# Buck.net
KiCad netlist of a schematic drawn in EAGLE
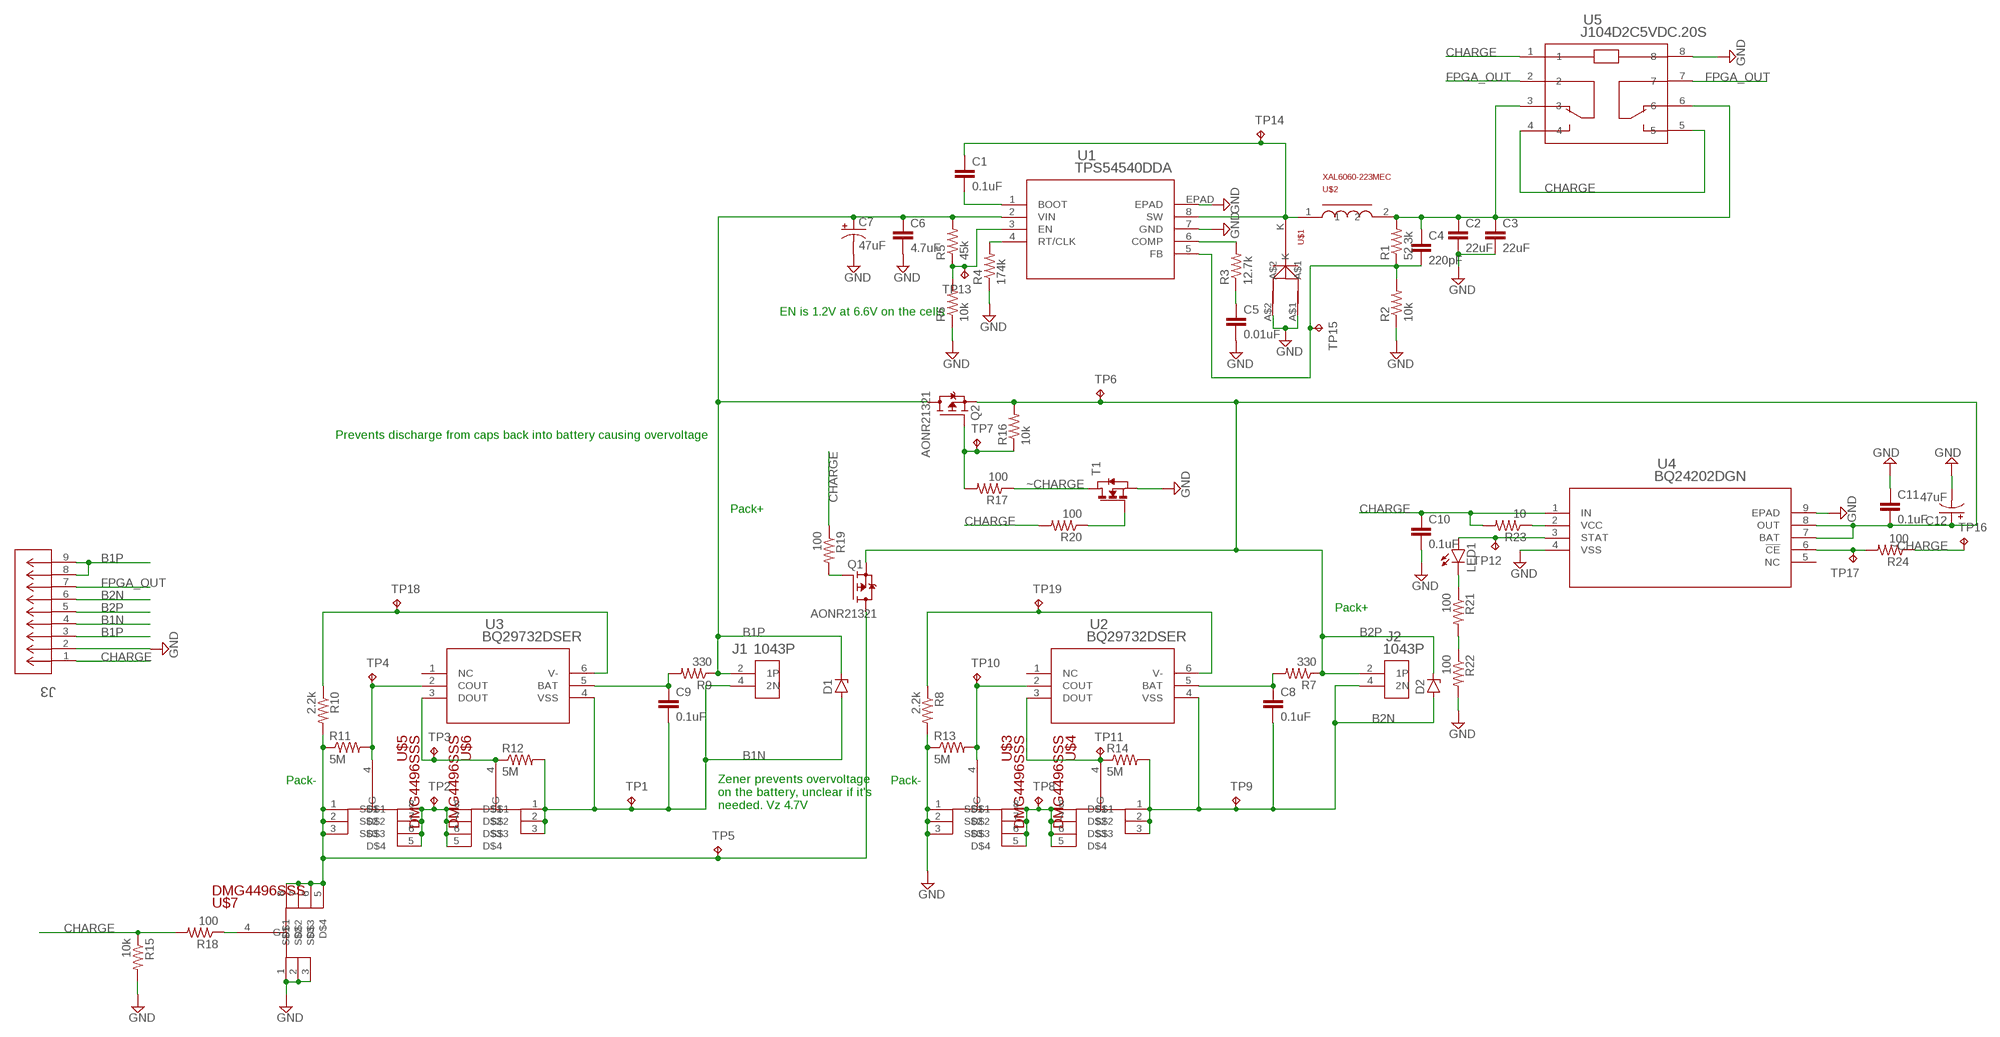
[diagram p0: schematic, sheet 1]

(export (version "E")
  (design (tool "Eeschema 10.0.6"))
  (components
    (comp (ref "C1")
      (value "0.1uF")
      (footprint "eagle-import:C0603")
      (libsource (lib "eagle-import") (part "C-EUC0603"))
    )
    (comp (ref "C2")
      (value "22uF")
      (footprint "eagle-import:C0603")
      (libsource (lib "eagle-import") (part "C-EUC0603"))
    )
    (comp (ref "C3")
      (value "22uF")
      (footprint "eagle-import:C0603")
      (libsource (lib "eagle-import") (part "C-EUC0603"))
    )
    (comp (ref "C4")
      (value "220pF")
      (footprint "eagle-import:C0603")
      (libsource (lib "eagle-import") (part "C-EUC0603"))
    )
    (comp (ref "C5")
      (value "0.01uF")
      (footprint "eagle-import:C0603")
      (libsource (lib "eagle-import") (part "C-EUC0603"))
    )
    (comp (ref "C6")
      (value "4.7uF")
      (footprint "eagle-import:C0603")
      (libsource (lib "eagle-import") (part "C-EUC0603"))
    )
    (comp (ref "C7")
      (value "47uF")
      (footprint "eagle-import:E2-5")
      (libsource (lib "eagle-import") (part "CPOL-USE2-5"))
    )
    (comp (ref "C8")
      (value "0.1uF")
      (footprint "eagle-import:C0603")
      (libsource (lib "eagle-import") (part "C-EUC0603"))
    )
    (comp (ref "C9")
      (value "0.1uF")
      (footprint "eagle-import:C0603")
      (libsource (lib "eagle-import") (part "C-EUC0603"))
    )
    (comp (ref "C10")
      (value "0.1uF")
      (footprint "eagle-import:C0603")
      (libsource (lib "eagle-import") (part "C-EUC0603"))
    )
    (comp (ref "C11")
      (value "0.1uF")
      (footprint "eagle-import:C0603")
      (libsource (lib "eagle-import") (part "C-EUC0603"))
    )
    (comp (ref "C12")
      (value "47uF")
      (footprint "eagle-import:E2-5")
      (libsource (lib "eagle-import") (part "CPOL-USE2-5"))
    )
    (comp (ref "D1")
      (value "ZENER-DIODESOT23")
      (footprint "eagle-import:SOT23")
      (libsource (lib "eagle-import") (part "ZENER-DIODESOT23"))
    )
    (comp (ref "D2")
      (value "ZENER-DIODESOT23")
      (footprint "eagle-import:SOT23")
      (libsource (lib "eagle-import") (part "ZENER-DIODESOT23"))
    )
    (comp (ref "J1")
      (value "1043P")
      (footprint "eagle-import:CONN2_1043P_KEY")
      (fields (field (name "COPYRIGHT") "Copyright (C) 2022 Ultra Librarian. All rights reserved."))
      (libsource (lib "eagle-import") (part "1043P"))
    )
    (comp (ref "J2")
      (value "1043P")
      (footprint "eagle-import:CONN2_1043P_KEY")
      (fields (field (name "COPYRIGHT") "Copyright (C) 2022 Ultra Librarian. All rights reserved."))
      (libsource (lib "eagle-import") (part "1043P"))
    )
    (comp (ref "J3")
      (value "L77TSEH09SOL2")
      (footprint "eagle-import:CONN_L77TSEH09SOL2_AMP")
      (fields (field (name "COPYRIGHT") "Copyright (C) 2022 Ultra Librarian. All rights reserved."))
      (libsource (lib "eagle-import") (part "L77TSEH09SOL2"))
    )
    (comp (ref "LED1")
      (value "LEDCHIPLED_0603")
      (footprint "eagle-import:CHIPLED_0603")
      (libsource (lib "eagle-import") (part "LEDCHIPLED_0603"))
    )
    (comp (ref "Q1")
      (value "AONR21321")
      (footprint "eagle-import:TRANS_AONR21321")
      (fields (field (name "DIGI-KEY_PART_NUMBER") "785-1797-2-ND") (field (name "MF") "Alpha &"))
      (libsource (lib "eagle-import") (part "AONR21321"))
    )
    (comp (ref "Q2")
      (value "AONR21321")
      (footprint "eagle-import:TRANS_AONR21321")
      (fields (field (name "DIGI-KEY_PART_NUMBER") "785-1797-2-ND") (field (name "MF") "Alpha &"))
      (libsource (lib "eagle-import") (part "AONR21321"))
    )
    (comp (ref "R1")
      (value "52.3k")
      (footprint "eagle-import:R0603")
      (libsource (lib "eagle-import") (part "R-US_R0603"))
    )
    (comp (ref "R2")
      (value "10k")
      (footprint "eagle-import:R0603")
      (libsource (lib "eagle-import") (part "R-US_R0603"))
    )
    (comp (ref "R3")
      (value "12.7k")
      (footprint "eagle-import:R0603")
      (libsource (lib "eagle-import") (part "R-US_R0603"))
    )
    (comp (ref "R4")
      (value "174k")
      (footprint "eagle-import:R0603")
      (libsource (lib "eagle-import") (part "R-US_R0603"))
    )
    (comp (ref "R5")
      (value "45k")
      (footprint "eagle-import:R0603")
      (libsource (lib "eagle-import") (part "R-US_R0603"))
    )
    (comp (ref "R6")
      (value "10k")
      (footprint "eagle-import:R0603")
      (libsource (lib "eagle-import") (part "R-US_R0603"))
    )
    (comp (ref "R7")
      (value "330")
      (footprint "eagle-import:R0603")
      (libsource (lib "eagle-import") (part "R-US_R0603"))
    )
    (comp (ref "R8")
      (value "2.2k")
      (footprint "eagle-import:R0603")
      (libsource (lib "eagle-import") (part "R-US_R0603"))
    )
    (comp (ref "R9")
      (value "330")
      (footprint "eagle-import:R0603")
      (libsource (lib "eagle-import") (part "R-US_R0603"))
    )
    (comp (ref "R10")
      (value "2.2k")
      (footprint "eagle-import:R0603")
      (libsource (lib "eagle-import") (part "R-US_R0603"))
    )
    (comp (ref "R11")
      (value "5M")
      (footprint "eagle-import:R0603")
      (libsource (lib "eagle-import") (part "R-US_R0603"))
    )
    (comp (ref "R12")
      (value "5M")
      (footprint "eagle-import:R0603")
      (libsource (lib "eagle-import") (part "R-US_R0603"))
    )
    (comp (ref "R13")
      (value "5M")
      (footprint "eagle-import:R0603")
      (libsource (lib "eagle-import") (part "R-US_R0603"))
    )
    (comp (ref "R14")
      (value "5M")
      (footprint "eagle-import:R0603")
      (libsource (lib "eagle-import") (part "R-US_R0603"))
    )
    (comp (ref "R15")
      (value "10k")
      (footprint "eagle-import:R0603")
      (libsource (lib "eagle-import") (part "R-US_R0603"))
    )
    (comp (ref "R16")
      (value "10k")
      (footprint "eagle-import:R0603")
      (libsource (lib "eagle-import") (part "R-US_R0603"))
    )
    (comp (ref "R17")
      (value "100")
      (footprint "eagle-import:R0603")
      (libsource (lib "eagle-import") (part "R-US_R0603"))
    )
    (comp (ref "R18")
      (value "100")
      (footprint "eagle-import:R0603")
      (libsource (lib "eagle-import") (part "R-US_R0603"))
    )
    (comp (ref "R19")
      (value "100")
      (footprint "eagle-import:R0603")
      (libsource (lib "eagle-import") (part "R-US_R0603"))
    )
    (comp (ref "R20")
      (value "100")
      (footprint "eagle-import:R0603")
      (libsource (lib "eagle-import") (part "R-US_R0603"))
    )
    (comp (ref "R21")
      (value "100")
      (footprint "eagle-import:R0603")
      (libsource (lib "eagle-import") (part "R-US_R0603"))
    )
    (comp (ref "R22")
      (value "100")
      (footprint "eagle-import:R0603")
      (libsource (lib "eagle-import") (part "R-US_R0603"))
    )
    (comp (ref "R23")
      (value "10")
      (footprint "eagle-import:R0603")
      (libsource (lib "eagle-import") (part "R-US_R0603"))
    )
    (comp (ref "R24")
      (value "100")
      (footprint "eagle-import:R0603")
      (libsource (lib "eagle-import") (part "R-US_R0603"))
    )
    (comp (ref "T1")
      (value "NMOSSOT23")
      (footprint "eagle-import:SOT-23")
      (libsource (lib "eagle-import") (part "NMOSSOT23"))
    )
    (comp (ref "TP1")
      (value "TPTP13R")
      (footprint "eagle-import:TP13R")
      (libsource (lib "eagle-import") (part "TPTP13R"))
    )
    (comp (ref "TP2")
      (value "TPTP13R")
      (footprint "eagle-import:TP13R")
      (libsource (lib "eagle-import") (part "TPTP13R"))
    )
    (comp (ref "TP3")
      (value "TPTP13R")
      (footprint "eagle-import:TP13R")
      (libsource (lib "eagle-import") (part "TPTP13R"))
    )
    (comp (ref "TP4")
      (value "TPTP13R")
      (footprint "eagle-import:TP13R")
      (libsource (lib "eagle-import") (part "TPTP13R"))
    )
    (comp (ref "TP5")
      (value "TPTP13R")
      (footprint "eagle-import:TP13R")
      (libsource (lib "eagle-import") (part "TPTP13R"))
    )
    (comp (ref "TP6")
      (value "TPTP13R")
      (footprint "eagle-import:TP13R")
      (libsource (lib "eagle-import") (part "TPTP13R"))
    )
    (comp (ref "TP7")
      (value "TPTP13R")
      (footprint "eagle-import:TP13R")
      (libsource (lib "eagle-import") (part "TPTP13R"))
    )
    (comp (ref "TP8")
      (value "TPTP13R")
      (footprint "eagle-import:TP13R")
      (libsource (lib "eagle-import") (part "TPTP13R"))
    )
    (comp (ref "TP9")
      (value "TPTP13R")
      (footprint "eagle-import:TP13R")
      (libsource (lib "eagle-import") (part "TPTP13R"))
    )
    (comp (ref "TP10")
      (value "TPTP13R")
      (footprint "eagle-import:TP13R")
      (libsource (lib "eagle-import") (part "TPTP13R"))
    )
    (comp (ref "TP11")
      (value "TPTP13R")
      (footprint "eagle-import:TP13R")
      (libsource (lib "eagle-import") (part "TPTP13R"))
    )
    (comp (ref "TP12")
      (value "TPTP13R")
      (footprint "eagle-import:TP13R")
      (libsource (lib "eagle-import") (part "TPTP13R"))
    )
    (comp (ref "TP13")
      (value "TPTP13R")
      (footprint "eagle-import:TP13R")
      (libsource (lib "eagle-import") (part "TPTP13R"))
    )
    (comp (ref "TP14")
      (value "TPTP13R")
      (footprint "eagle-import:TP13R")
      (libsource (lib "eagle-import") (part "TPTP13R"))
    )
    (comp (ref "TP15")
      (value "TPTP13R")
      (footprint "eagle-import:TP13R")
      (libsource (lib "eagle-import") (part "TPTP13R"))
    )
    (comp (ref "TP16")
      (value "TPTP13R")
      (footprint "eagle-import:TP13R")
      (libsource (lib "eagle-import") (part "TPTP13R"))
    )
    (comp (ref "TP17")
      (value "TPTP13R")
      (footprint "eagle-import:TP13R")
      (libsource (lib "eagle-import") (part "TPTP13R"))
    )
    (comp (ref "TP18")
      (value "TPTP13R")
      (footprint "eagle-import:TP13R")
      (libsource (lib "eagle-import") (part "TPTP13R"))
    )
    (comp (ref "TP19")
      (value "TPTP13R")
      (footprint "eagle-import:TP13R")
      (libsource (lib "eagle-import") (part "TPTP13R"))
    )
    (comp (ref "U$1")
      (value "SS3P5LHM3_A/H")
      (footprint "eagle-import:TO-227A")
      (libsource (lib "eagle-import") (part "SS3P5LHM3_A/H"))
    )
    (comp (ref "U$2")
      (value "XAL6060-223MEC")
      (footprint "eagle-import:XAL6060")
      (libsource (lib "eagle-import") (part "XAL6060-223MEC"))
    )
    (comp (ref "U$3")
      (value "DMG4496SSS")
      (footprint "eagle-import:SO-8")
      (libsource (lib "eagle-import") (part "DMG4496SSS"))
    )
    (comp (ref "U$4")
      (value "DMG4496SSS")
      (footprint "eagle-import:SO-8")
      (libsource (lib "eagle-import") (part "DMG4496SSS"))
    )
    (comp (ref "U$5")
      (value "DMG4496SSS")
      (footprint "eagle-import:SO-8")
      (libsource (lib "eagle-import") (part "DMG4496SSS"))
    )
    (comp (ref "U$6")
      (value "DMG4496SSS")
      (footprint "eagle-import:SO-8")
      (libsource (lib "eagle-import") (part "DMG4496SSS"))
    )
    (comp (ref "U$7")
      (value "DMG4496SSS")
      (footprint "eagle-import:SO-8")
      (libsource (lib "eagle-import") (part "DMG4496SSS"))
    )
    (comp (ref "U1")
      (value "TPS54540DDA")
      (footprint "eagle-import:DDA8_3P1X2P4_TEX")
      (fields (field (name "COPYRIGHT") "Copyright (C) 2022 Ultra Librarian. All rights reserved."))
      (libsource (lib "eagle-import") (part "TPS54540DDA"))
    )
    (comp (ref "U2")
      (value "BQ29732DSER")
      (footprint "eagle-import:DSE6_TEX")
      (fields (field (name "COPYRIGHT") "Copyright (C) 2022 Ultra Librarian. All rights reserved."))
      (libsource (lib "eagle-import") (part "BQ29732DSER"))
    )
    (comp (ref "U3")
      (value "BQ29732DSER")
      (footprint "eagle-import:DSE6_TEX")
      (fields (field (name "COPYRIGHT") "Copyright (C) 2022 Ultra Librarian. All rights reserved."))
      (libsource (lib "eagle-import") (part "BQ29732DSER"))
    )
    (comp (ref "U4")
      (value "BQ24202DGN")
      (footprint "eagle-import:DGN8_1P57X1P89")
      (fields (field (name "COPYRIGHT") "Copyright (C) 2022 Ultra Librarian. All rights reserved."))
      (libsource (lib "eagle-import") (part "BQ24202DGN"))
    )
    (comp (ref "U5")
      (value "J104D2C5VDC.20S")
      (footprint "eagle-import:RELAY8_J104D2C5VDC.20S_CRS")
      (fields (field (name "COPYRIGHT") "Copyright (C) 2022 Ultra Librarian. All rights reserved."))
      (libsource (lib "eagle-import") (part "J104D2C5VDC.20S"))
    )
  )
  (nets
    (net (code "1") (name "/B1N") (class "Default")
      (node (ref "C9") (pin "2") (pinfunction "2_2") (pintype "passive"))
      (node (ref "D1") (pin "1") (pinfunction "A_1") (pintype "passive"))
      (node (ref "J1") (pin "4") (pinfunction "2N_4") (pintype "passive"))
      (node (ref "J3") (pin "4") (pinfunction "4_4") (pintype "passive"))
      (node (ref "R12") (pin "2") (pinfunction "2_2") (pintype "passive"))
      (node (ref "TP1") (pin "TP") (pinfunction "TP_TP") (pintype "input"))
      (node (ref "U$6") (pin "1") (pinfunction "S$1_1") (pintype "power_in"))
      (node (ref "U$6") (pin "2") (pinfunction "S$2_2") (pintype "bidirectional"))
      (node (ref "U$6") (pin "3") (pinfunction "S$3_3") (pintype "bidirectional"))
      (node (ref "U3") (pin "4") (pinfunction "VSS_4") (pintype "power_in"))
    )
    (net (code "2") (name "/B1P") (class "Default")
      (node (ref "C6") (pin "1") (pinfunction "1_1") (pintype "passive"))
      (node (ref "C7") (pin "+") (pinfunction "+_+") (pintype "passive"))
      (node (ref "D1") (pin "3") (pinfunction "C_3") (pintype "passive"))
      (node (ref "J1") (pin "2") (pinfunction "1P_2") (pintype "passive"))
      (node (ref "J3") (pin "3") (pinfunction "3_3") (pintype "passive"))
      (node (ref "J3") (pin "8") (pinfunction "8_8") (pintype "passive"))
      (node (ref "J3") (pin "9") (pinfunction "9_9") (pintype "passive"))
      (node (ref "Q2") (pin "5") (pinfunction "D_5") (pintype "passive"))
      (node (ref "Q2") (pin "6") (pinfunction "D_6") (pintype "passive"))
      (node (ref "Q2") (pin "7") (pinfunction "D_7") (pintype "passive"))
      (node (ref "Q2") (pin "8") (pinfunction "D_8") (pintype "passive"))
      (node (ref "Q2") (pin "9") (pinfunction "D_9") (pintype "passive"))
      (node (ref "Q2") (pin "9_1") (pinfunction "D_9_1") (pintype "passive"))
      (node (ref "Q2") (pin "9_2") (pinfunction "D_9_2") (pintype "passive"))
      (node (ref "R5") (pin "2") (pinfunction "2_2") (pintype "passive"))
      (node (ref "R9") (pin "1") (pinfunction "1_1") (pintype "passive"))
      (node (ref "U1") (pin "2") (pinfunction "VIN_2") (pintype "input"))
    )
    (net (code "3") (name "/B2N") (class "Default")
      (node (ref "C8") (pin "2") (pinfunction "2_2") (pintype "passive"))
      (node (ref "D2") (pin "1") (pinfunction "A_1") (pintype "passive"))
      (node (ref "J2") (pin "4") (pinfunction "2N_4") (pintype "passive"))
      (node (ref "J3") (pin "6") (pinfunction "6_6") (pintype "passive"))
      (node (ref "R14") (pin "2") (pinfunction "2_2") (pintype "passive"))
      (node (ref "TP9") (pin "TP") (pinfunction "TP_TP") (pintype "input"))
      (node (ref "U$4") (pin "1") (pinfunction "S$1_1") (pintype "power_in"))
      (node (ref "U$4") (pin "2") (pinfunction "S$2_2") (pintype "bidirectional"))
      (node (ref "U$4") (pin "3") (pinfunction "S$3_3") (pintype "bidirectional"))
      (node (ref "U2") (pin "4") (pinfunction "VSS_4") (pintype "power_in"))
    )
    (net (code "4") (name "/B2P") (class "Default")
      (node (ref "C11") (pin "2") (pinfunction "2_2") (pintype "passive"))
      (node (ref "C12") (pin "+") (pinfunction "+_+") (pintype "passive"))
      (node (ref "D2") (pin "3") (pinfunction "C_3") (pintype "passive"))
      (node (ref "J2") (pin "2") (pinfunction "1P_2") (pintype "passive"))
      (node (ref "J3") (pin "5") (pinfunction "5_5") (pintype "passive"))
      (node (ref "Q1") (pin "1") (pinfunction "S_1") (pintype "passive"))
      (node (ref "Q1") (pin "2") (pinfunction "S_2") (pintype "passive"))
      (node (ref "Q1") (pin "3") (pinfunction "S_3") (pintype "passive"))
      (node (ref "Q2") (pin "1") (pinfunction "S_1") (pintype "passive"))
      (node (ref "Q2") (pin "2") (pinfunction "S_2") (pintype "passive"))
      (node (ref "Q2") (pin "3") (pinfunction "S_3") (pintype "passive"))
      (node (ref "R16") (pin "2") (pinfunction "2_2") (pintype "passive"))
      (node (ref "R7") (pin "1") (pinfunction "1_1") (pintype "passive"))
      (node (ref "TP6") (pin "TP") (pinfunction "TP_TP") (pintype "input"))
      (node (ref "U4") (pin "7") (pinfunction "BAT_7") (pintype "input"))
      (node (ref "U4") (pin "8") (pinfunction "OUT_8") (pintype "output"))
    )
    (net (code "5") (name "/CHARGE") (class "Default")
      (node (ref "C10") (pin "1") (pinfunction "1_1") (pintype "passive"))
      (node (ref "J3") (pin "1") (pinfunction "1_1") (pintype "passive"))
      (node (ref "R15") (pin "1") (pinfunction "1_1") (pintype "passive"))
      (node (ref "R18") (pin "2") (pinfunction "2_2") (pintype "passive"))
      (node (ref "R19") (pin "1") (pinfunction "1_1") (pintype "passive"))
      (node (ref "R20") (pin "2") (pinfunction "2_2") (pintype "passive"))
      (node (ref "R23") (pin "2") (pinfunction "2_2") (pintype "passive"))
      (node (ref "U4") (pin "1") (pinfunction "IN_1") (pintype "input"))
      (node (ref "U5") (pin "1") (pinfunction "1_1") (pintype "passive"))
      (node (ref "U5") (pin "4") (pinfunction "4_4") (pintype "passive"))
      (node (ref "U5") (pin "5") (pinfunction "5_5") (pintype "passive"))
    )
    (net (code "6") (name "/FPGA_OUT") (class "Default")
      (node (ref "J3") (pin "7") (pinfunction "7_7") (pintype "passive"))
      (node (ref "U5") (pin "2") (pinfunction "2_2") (pintype "passive"))
      (node (ref "U5") (pin "7") (pinfunction "7_7") (pintype "passive"))
    )
    (net (code "7") (name "/~{CHARGE}") (class "Default")
      (node (ref "R17") (pin "1") (pinfunction "1_1") (pintype "passive"))
      (node (ref "R24") (pin "1") (pinfunction "1_1") (pintype "passive"))
      (node (ref "T1") (pin "1") (pinfunction "D_1") (pintype "passive"))
      (node (ref "TP16") (pin "TP") (pinfunction "TP_TP") (pintype "input"))
    )
    (net (code "8") (name "GND") (class "Default")
      (node (ref "C10") (pin "2") (pinfunction "2_2") (pintype "passive"))
      (node (ref "C11") (pin "1") (pinfunction "1_1") (pintype "passive"))
      (node (ref "C12") (pin "-") (pinfunction "-_-") (pintype "passive"))
      (node (ref "C2") (pin "2") (pinfunction "2_2") (pintype "passive"))
      (node (ref "C3") (pin "2") (pinfunction "2_2") (pintype "passive"))
      (node (ref "C5") (pin "2") (pinfunction "2_2") (pintype "passive"))
      (node (ref "C6") (pin "2") (pinfunction "2_2") (pintype "passive"))
      (node (ref "C7") (pin "-") (pinfunction "-_-") (pintype "passive"))
      (node (ref "J3") (pin "2") (pinfunction "2_2") (pintype "passive"))
      (node (ref "R13") (pin "1") (pinfunction "1_1") (pintype "passive"))
      (node (ref "R15") (pin "2") (pinfunction "2_2") (pintype "passive"))
      (node (ref "R2") (pin "1") (pinfunction "1_1") (pintype "passive"))
      (node (ref "R22") (pin "2") (pinfunction "2_2") (pintype "passive"))
      (node (ref "R4") (pin "1") (pinfunction "1_1") (pintype "passive"))
      (node (ref "R6") (pin "1") (pinfunction "1_1") (pintype "passive"))
      (node (ref "R8") (pin "2") (pinfunction "2_2") (pintype "passive"))
      (node (ref "T1") (pin "2") (pinfunction "S_2") (pintype "passive"))
      (node (ref "U$1") (pin "A$1") (pinfunction "A$1_A$1") (pintype "bidirectional"))
      (node (ref "U$1") (pin "A$2") (pinfunction "A$2_A$2") (pintype "bidirectional"))
      (node (ref "U$3") (pin "1") (pinfunction "S$1_1") (pintype "power_in"))
      (node (ref "U$3") (pin "2") (pinfunction "S$2_2") (pintype "bidirectional"))
      (node (ref "U$3") (pin "3") (pinfunction "S$3_3") (pintype "bidirectional"))
      (node (ref "U$7") (pin "1") (pinfunction "S$1_1") (pintype "power_in"))
      (node (ref "U$7") (pin "2") (pinfunction "S$2_2") (pintype "bidirectional"))
      (node (ref "U$7") (pin "3") (pinfunction "S$3_3") (pintype "bidirectional"))
      (node (ref "U1") (pin "7") (pinfunction "GND_7") (pintype "power_in"))
      (node (ref "U1") (pin "EPAD") (pinfunction "EPAD_EPAD") (pintype "passive"))
      (node (ref "U4") (pin "4") (pinfunction "VSS_4") (pintype "power_in"))
      (node (ref "U4") (pin "9") (pinfunction "EPAD_9") (pintype "power_in"))
      (node (ref "U5") (pin "8") (pinfunction "8_8") (pintype "passive"))
    )
    (net (code "9") (name "Net-(C2-Pad1)") (class "Default")
      (node (ref "C2") (pin "1") (pinfunction "1_1") (pintype "passive"))
      (node (ref "C3") (pin "1") (pinfunction "1_1") (pintype "passive"))
      (node (ref "C4") (pin "1") (pinfunction "1_1") (pintype "passive"))
      (node (ref "R1") (pin "2") (pinfunction "2_2") (pintype "passive"))
      (node (ref "U$2") (pin "2") (pinfunction "2_2") (pintype "bidirectional"))
      (node (ref "U5") (pin "3") (pinfunction "3_3") (pintype "passive"))
      (node (ref "U5") (pin "6") (pinfunction "6_6") (pintype "passive"))
    )
    (net (code "10") (name "Net-(C5-Pad1)") (class "Default")
      (node (ref "C5") (pin "1") (pinfunction "1_1") (pintype "passive"))
      (node (ref "R3") (pin "1") (pinfunction "1_1") (pintype "passive"))
    )
    (net (code "11") (name "Net-(LED1-PadC)") (class "Default")
      (node (ref "LED1") (pin "C") (pinfunction "C_C") (pintype "passive"))
      (node (ref "R21") (pin "1") (pinfunction "1_1") (pintype "passive"))
    )
    (net (code "12") (name "Net-(Q1-G)") (class "Default")
      (node (ref "Q1") (pin "4") (pinfunction "G_4") (pintype "passive"))
      (node (ref "R19") (pin "2") (pinfunction "2_2") (pintype "passive"))
    )
    (net (code "13") (name "Net-(Q2-G)") (class "Default")
      (node (ref "Q2") (pin "4") (pinfunction "G_4") (pintype "passive"))
      (node (ref "R16") (pin "1") (pinfunction "1_1") (pintype "passive"))
      (node (ref "R17") (pin "2") (pinfunction "2_2") (pintype "passive"))
      (node (ref "TP7") (pin "TP") (pinfunction "TP_TP") (pintype "input"))
    )
    (net (code "14") (name "Net-(R21-Pad2)") (class "Default")
      (node (ref "R21") (pin "2") (pinfunction "2_2") (pintype "passive"))
      (node (ref "R22") (pin "1") (pinfunction "1_1") (pintype "passive"))
    )
    (net (code "15") (name "Net-(T1-G)") (class "Default")
      (node (ref "R20") (pin "1") (pinfunction "1_1") (pintype "passive"))
      (node (ref "T1") (pin "3") (pinfunction "G_3") (pintype "passive"))
    )
    (net (code "16") (name "Net-(U$3-D$1)") (class "Default")
      (node (ref "TP8") (pin "TP") (pinfunction "TP_TP") (pintype "input"))
      (node (ref "U$3") (pin "5") (pinfunction "D$4_5") (pintype "bidirectional"))
      (node (ref "U$3") (pin "6") (pinfunction "D$3_6") (pintype "bidirectional"))
      (node (ref "U$3") (pin "7") (pinfunction "D$2_7") (pintype "bidirectional"))
      (node (ref "U$3") (pin "8") (pinfunction "D$1_8") (pintype "power_in"))
      (node (ref "U$4") (pin "5") (pinfunction "D$4_5") (pintype "bidirectional"))
      (node (ref "U$4") (pin "6") (pinfunction "D$3_6") (pintype "bidirectional"))
      (node (ref "U$4") (pin "7") (pinfunction "D$2_7") (pintype "bidirectional"))
      (node (ref "U$4") (pin "8") (pinfunction "D$1_8") (pintype "power_in"))
    )
    (net (code "17") (name "Net-(U$3-G)") (class "Default")
      (node (ref "R13") (pin "2") (pinfunction "2_2") (pintype "passive"))
      (node (ref "TP10") (pin "TP") (pinfunction "TP_TP") (pintype "input"))
      (node (ref "U$3") (pin "4") (pinfunction "G_4") (pintype "power_in"))
      (node (ref "U2") (pin "2") (pinfunction "COUT_2") (pintype "output"))
    )
    (net (code "18") (name "Net-(U$4-G)") (class "Default")
      (node (ref "R14") (pin "1") (pinfunction "1_1") (pintype "passive"))
      (node (ref "TP11") (pin "TP") (pinfunction "TP_TP") (pintype "input"))
      (node (ref "U$4") (pin "4") (pinfunction "G_4") (pintype "power_in"))
      (node (ref "U2") (pin "3") (pinfunction "DOUT_3") (pintype "output"))
    )
    (net (code "19") (name "Net-(U$5-D$1)") (class "Default")
      (node (ref "TP2") (pin "TP") (pinfunction "TP_TP") (pintype "input"))
      (node (ref "U$5") (pin "5") (pinfunction "D$4_5") (pintype "bidirectional"))
      (node (ref "U$5") (pin "6") (pinfunction "D$3_6") (pintype "bidirectional"))
      (node (ref "U$5") (pin "7") (pinfunction "D$2_7") (pintype "bidirectional"))
      (node (ref "U$5") (pin "8") (pinfunction "D$1_8") (pintype "power_in"))
      (node (ref "U$6") (pin "5") (pinfunction "D$4_5") (pintype "bidirectional"))
      (node (ref "U$6") (pin "6") (pinfunction "D$3_6") (pintype "bidirectional"))
      (node (ref "U$6") (pin "7") (pinfunction "D$2_7") (pintype "bidirectional"))
      (node (ref "U$6") (pin "8") (pinfunction "D$1_8") (pintype "power_in"))
    )
    (net (code "20") (name "Net-(U$5-G)") (class "Default")
      (node (ref "R11") (pin "2") (pinfunction "2_2") (pintype "passive"))
      (node (ref "TP4") (pin "TP") (pinfunction "TP_TP") (pintype "input"))
      (node (ref "U$5") (pin "4") (pinfunction "G_4") (pintype "power_in"))
      (node (ref "U3") (pin "2") (pinfunction "COUT_2") (pintype "output"))
    )
    (net (code "21") (name "Net-(U$5-S$1)") (class "Default")
      (node (ref "Q1") (pin "5") (pinfunction "D_5") (pintype "passive"))
      (node (ref "Q1") (pin "6") (pinfunction "D_6") (pintype "passive"))
      (node (ref "Q1") (pin "7") (pinfunction "D_7") (pintype "passive"))
      (node (ref "Q1") (pin "8") (pinfunction "D_8") (pintype "passive"))
      (node (ref "Q1") (pin "9") (pinfunction "D_9") (pintype "passive"))
      (node (ref "Q1") (pin "9_1") (pinfunction "D_9_1") (pintype "passive"))
      (node (ref "Q1") (pin "9_2") (pinfunction "D_9_2") (pintype "passive"))
      (node (ref "R10") (pin "2") (pinfunction "2_2") (pintype "passive"))
      (node (ref "R11") (pin "1") (pinfunction "1_1") (pintype "passive"))
      (node (ref "TP5") (pin "TP") (pinfunction "TP_TP") (pintype "input"))
      (node (ref "U$5") (pin "1") (pinfunction "S$1_1") (pintype "power_in"))
      (node (ref "U$5") (pin "2") (pinfunction "S$2_2") (pintype "bidirectional"))
      (node (ref "U$5") (pin "3") (pinfunction "S$3_3") (pintype "bidirectional"))
      (node (ref "U$7") (pin "5") (pinfunction "D$4_5") (pintype "bidirectional"))
      (node (ref "U$7") (pin "6") (pinfunction "D$3_6") (pintype "bidirectional"))
      (node (ref "U$7") (pin "7") (pinfunction "D$2_7") (pintype "bidirectional"))
      (node (ref "U$7") (pin "8") (pinfunction "D$1_8") (pintype "power_in"))
    )
    (net (code "22") (name "Net-(U$6-G)") (class "Default")
      (node (ref "R12") (pin "1") (pinfunction "1_1") (pintype "passive"))
      (node (ref "TP3") (pin "TP") (pinfunction "TP_TP") (pintype "input"))
      (node (ref "U$6") (pin "4") (pinfunction "G_4") (pintype "power_in"))
      (node (ref "U3") (pin "3") (pinfunction "DOUT_3") (pintype "output"))
    )
    (net (code "23") (name "Net-(U$7-G)") (class "Default")
      (node (ref "R18") (pin "1") (pinfunction "1_1") (pintype "passive"))
      (node (ref "U$7") (pin "4") (pinfunction "G_4") (pintype "power_in"))
    )
    (net (code "24") (name "Net-(U1-BOOT)") (class "Default")
      (node (ref "C1") (pin "2") (pinfunction "2_2") (pintype "passive"))
      (node (ref "U1") (pin "1") (pinfunction "BOOT_1") (pintype "output"))
    )
    (net (code "25") (name "Net-(U1-COMP)") (class "Default")
      (node (ref "R3") (pin "2") (pinfunction "2_2") (pintype "passive"))
      (node (ref "U1") (pin "6") (pinfunction "COMP_6") (pintype "output"))
    )
    (net (code "26") (name "Net-(U1-EN)") (class "Default")
      (node (ref "R5") (pin "1") (pinfunction "1_1") (pintype "passive"))
      (node (ref "R6") (pin "2") (pinfunction "2_2") (pintype "passive"))
      (node (ref "TP13") (pin "TP") (pinfunction "TP_TP") (pintype "input"))
      (node (ref "U1") (pin "3") (pinfunction "EN_3") (pintype "input"))
    )
    (net (code "27") (name "Net-(U1-FB)") (class "Default")
      (node (ref "C4") (pin "2") (pinfunction "2_2") (pintype "passive"))
      (node (ref "R1") (pin "1") (pinfunction "1_1") (pintype "passive"))
      (node (ref "R2") (pin "2") (pinfunction "2_2") (pintype "passive"))
      (node (ref "TP15") (pin "TP") (pinfunction "TP_TP") (pintype "input"))
      (node (ref "U1") (pin "5") (pinfunction "FB_5") (pintype "input"))
    )
    (net (code "28") (name "Net-(U1-RT{slash}CLK)") (class "Default")
      (node (ref "R4") (pin "2") (pinfunction "2_2") (pintype "passive"))
      (node (ref "U1") (pin "4") (pinfunction "RT/CLK_4") (pintype "input"))
    )
    (net (code "29") (name "Net-(U1-SW)") (class "Default")
      (node (ref "C1") (pin "1") (pinfunction "1_1") (pintype "passive"))
      (node (ref "TP14") (pin "TP") (pinfunction "TP_TP") (pintype "input"))
      (node (ref "U$1") (pin "K") (pinfunction "K_K") (pintype "bidirectional"))
      (node (ref "U$2") (pin "1") (pinfunction "1_1") (pintype "bidirectional"))
      (node (ref "U1") (pin "8") (pinfunction "SW_8") (pintype "input"))
    )
    (net (code "30") (name "Net-(U2-BAT)") (class "Default")
      (node (ref "C8") (pin "1") (pinfunction "1_1") (pintype "passive"))
      (node (ref "R7") (pin "2") (pinfunction "2_2") (pintype "passive"))
      (node (ref "U2") (pin "5") (pinfunction "BAT_5") (pintype "passive"))
    )
    (net (code "31") (name "Net-(U2-V-)") (class "Default")
      (node (ref "R8") (pin "1") (pinfunction "1_1") (pintype "passive"))
      (node (ref "TP19") (pin "TP") (pinfunction "TP_TP") (pintype "input"))
      (node (ref "U2") (pin "6") (pinfunction "V-_6") (pintype "power_in"))
    )
    (net (code "32") (name "Net-(U3-BAT)") (class "Default")
      (node (ref "C9") (pin "1") (pinfunction "1_1") (pintype "passive"))
      (node (ref "R9") (pin "2") (pinfunction "2_2") (pintype "passive"))
      (node (ref "U3") (pin "5") (pinfunction "BAT_5") (pintype "passive"))
    )
    (net (code "33") (name "Net-(U3-V-)") (class "Default")
      (node (ref "R10") (pin "1") (pinfunction "1_1") (pintype "passive"))
      (node (ref "TP18") (pin "TP") (pinfunction "TP_TP") (pintype "input"))
      (node (ref "U3") (pin "6") (pinfunction "V-_6") (pintype "power_in"))
    )
    (net (code "34") (name "Net-(U4-STAT)") (class "Default")
      (node (ref "LED1") (pin "A") (pinfunction "A_A") (pintype "passive"))
      (node (ref "TP12") (pin "TP") (pinfunction "TP_TP") (pintype "input"))
      (node (ref "U4") (pin "3") (pinfunction "STAT_3") (pintype "output"))
    )
    (net (code "35") (name "Net-(U4-VCC)") (class "Default")
      (node (ref "R23") (pin "1") (pinfunction "1_1") (pintype "passive"))
      (node (ref "U4") (pin "2") (pinfunction "VCC_2") (pintype "power_in"))
    )
    (net (code "36") (name "Net-(U4-~{CE})") (class "Default")
      (node (ref "R24") (pin "2") (pinfunction "2_2") (pintype "passive"))
      (node (ref "TP17") (pin "TP") (pinfunction "TP_TP") (pintype "input"))
      (node (ref "U4") (pin "6") (pinfunction "~{CE}_6") (pintype "input"))
    )
    (net (code "37") (name "unconnected-(U2-NC-Pad1)") (class "Default")
      (node (ref "U2") (pin "1") (pinfunction "NC_1") (pintype "no_connect"))
    )
    (net (code "38") (name "unconnected-(U3-NC-Pad1)") (class "Default")
      (node (ref "U3") (pin "1") (pinfunction "NC_1") (pintype "no_connect"))
    )
    (net (code "39") (name "unconnected-(U4-NC-Pad5)") (class "Default")
      (node (ref "U4") (pin "5") (pinfunction "NC_5") (pintype "no_connect"))
    )
  )
)
